# MPU6050.net
KiCad netlist of a schematic drawn in Altium Designer
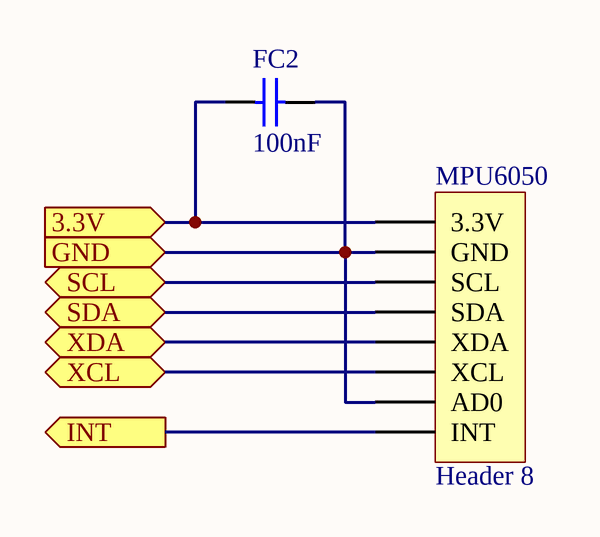
[diagram p0: MPU6050.SchDoc]

(export (version "E")
  (design (tool "Eeschema 10.0.6"))
  (components
    (comp (ref "FC2")
      (value "100nF")
      (footprint "RAD-0.3")
      (description "Capacitor")
      (fields (field (name "PUBLISHER") "Altium Limited"))
      (libsource (lib "Miscellaneous Devices") (part "Cap"))
    )
    (comp (ref "MPU6050")
      (value "Header 8")
      (footprint "HDR1X8")
      (description "Header, 8-Pin")
      (fields (field (name "PUBLISHER") "Altium Limited"))
      (libsource (lib "Miscellaneous Connectors") (part "Header 8"))
    )
  )
  (nets
    (net (code "1") (name "/3.3V") (class "Default")
      (node (ref "FC2") (pin "1") (pinfunction "1_1") (pintype "passive"))
      (node (ref "MPU6050") (pin "1") (pinfunction "3.3V_1") (pintype "passive"))
    )
    (net (code "2") (name "/GND") (class "Default")
      (node (ref "FC2") (pin "2") (pinfunction "2_2") (pintype "passive"))
      (node (ref "MPU6050") (pin "2") (pinfunction "GND_2") (pintype "passive"))
      (node (ref "MPU6050") (pin "7") (pinfunction "AD0_7") (pintype "passive"))
    )
    (net (code "3") (name "/INT") (class "Default")
      (node (ref "MPU6050") (pin "8") (pinfunction "INT_8") (pintype "passive"))
    )
    (net (code "4") (name "/SCL") (class "Default")
      (node (ref "MPU6050") (pin "3") (pinfunction "SCL_3") (pintype "passive"))
    )
    (net (code "5") (name "/SDA") (class "Default")
      (node (ref "MPU6050") (pin "4") (pinfunction "SDA_4") (pintype "passive"))
    )
    (net (code "6") (name "/XCL") (class "Default")
      (node (ref "MPU6050") (pin "6") (pinfunction "XCL_6") (pintype "passive"))
    )
    (net (code "7") (name "/XDA") (class "Default")
      (node (ref "MPU6050") (pin "5") (pinfunction "XDA_5") (pintype "passive"))
    )
  )
)
